# PLC_NanoPI.net
KiCad netlist of a schematic drawn in Altium Designer
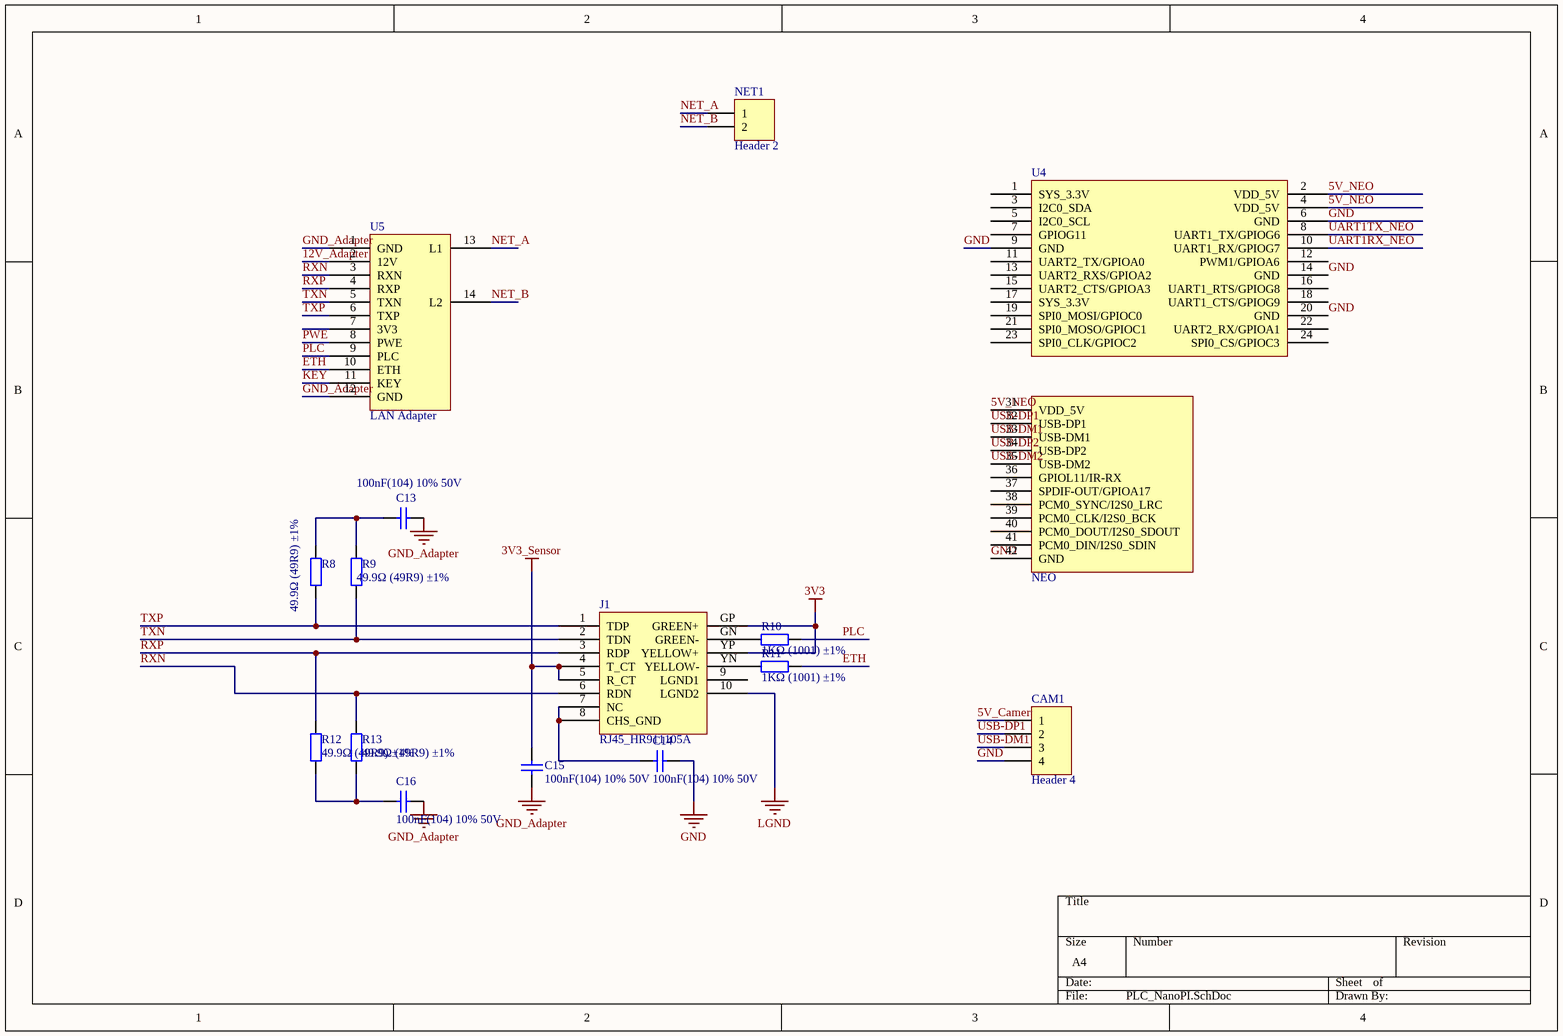
[diagram p0: PLC_NanoPI.SchDoc]

(export (version "E")
  (design (tool "Eeschema 10.0.6"))
  (components
    (comp (ref "C13")
      (value "100nF(104) 10% 50V")
      (footprint "0603_C")
      (description "贴片电容")
      (libsource (lib "Miscellaneous Devices LC") (part "0805 100nF(104) 10% 50V"))
    )
    (comp (ref "C14")
      (value "100nF(104) 10% 50V")
      (footprint "0603-cap")
      (description "贴片电容")
      (libsource (lib "Miscellaneous Devices LC") (part "0805 100nF(104) 10% 50V"))
    )
    (comp (ref "C15")
      (value "100nF(104) 10% 50V")
      (footprint "0603_C")
      (description "贴片电容")
      (libsource (lib "Miscellaneous Devices LC") (part "0805 100nF(104) 10% 50V"))
    )
    (comp (ref "C16")
      (value "100nF(104) 10% 50V")
      (footprint "0603_C")
      (description "贴片电容")
      (libsource (lib "Miscellaneous Devices LC") (part "0805 100nF(104) 10% 50V"))
    )
    (comp (ref "CAM1")
      (value "Header 4")
      (footprint "XH2.54_4P")
      (description "Header, 4-Pin")
      (fields (field (name "PUBLISHER") "Altium Limited"))
      (libsource (lib "Miscellaneous Connectors") (part "Header 4"))
    )
    (comp (ref "J1")
      (value "RJ45_HR911105A")
      (footprint "RJ45_3")
      (libsource (lib "RJ45") (part "RJ45_HR911105A"))
    )
    (comp (ref "NET1")
      (value "Header 2")
      (footprint "XH2.54_2P")
      (description "Header, 2-Pin")
      (fields (field (name "PUBLISHER") "Altium Limited"))
      (libsource (lib "Miscellaneous Connectors") (part "Header 2"))
    )
    (comp (ref "R8")
      (value "49.9Ω (49R9) ±1%")
      (footprint "0603_R")
      (description "贴片电阻")
      (libsource (lib "Miscellaneous Devices LC") (part "0805 49.9Ω (49R9) 1%"))
    )
    (comp (ref "R9")
      (value "49.9Ω (49R9) ±1%")
      (footprint "0603_R")
      (description "贴片电阻")
      (libsource (lib "Miscellaneous Devices LC") (part "0805 49.9Ω (49R9) 1%"))
    )
    (comp (ref "R10")
      (value "1KΩ (1001) ±1%")
      (footprint "0603_R")
      (description "贴片电阻")
      (libsource (lib "Miscellaneous Devices LC") (part "0603 1KΩ (1001) 1%"))
    )
    (comp (ref "R11")
      (value "1KΩ (1001) ±1%")
      (footprint "0603_R")
      (description "贴片电阻")
      (libsource (lib "Miscellaneous Devices LC") (part "0603 1KΩ (1001) 1%"))
    )
    (comp (ref "R12")
      (value "49.9Ω (49R9) ±1%")
      (footprint "0603_R")
      (description "贴片电阻")
      (libsource (lib "Miscellaneous Devices LC") (part "0805 49.9Ω (49R9) 1%"))
    )
    (comp (ref "R13")
      (value "49.9Ω (49R9) ±1%")
      (footprint "0603_R")
      (description "贴片电阻")
      (libsource (lib "Miscellaneous Devices LC") (part "0805 49.9Ω (49R9) 1%"))
    )
    (comp (ref "U4") (value "NEO") (footprint "NanoPiNEO") (libsource (lib "NanoPi") (part "NanoPiNEO")))
    (comp (ref "U5")
      (value "LAN Adapter")
      (footprint "LAN Adapter")
      (libsource (lib "Adapter") (part "LAN Adapter"))
    )
  )
  (nets
    (net (code "1") (name "/5V_Camera") (class "Default")
      (node (ref "CAM1") (pin "1") (pinfunction "1_1") (pintype "passive"))
    )
    (net (code "2") (name "/5V_NEO") (class "Default")
      (node (ref "U4") (pin "2") (pinfunction "VDD_5V_2") (pintype "passive"))
      (node (ref "U4") (pin "31") (pinfunction "VDD_5V_31") (pintype "passive"))
      (node (ref "U4") (pin "4") (pinfunction "VDD_5V_4") (pintype "passive"))
    )
    (net (code "3") (name "/12V_Adapter") (class "Default")
      (node (ref "U5") (pin "2") (pinfunction "12V_2") (pintype "passive"))
    )
    (net (code "4") (name "/ETH") (class "Default")
      (node (ref "R11") (pin "2") (pinfunction "2_2") (pintype "passive"))
      (node (ref "U5") (pin "10") (pinfunction "ETH_10") (pintype "passive"))
    )
    (net (code "5") (name "/KEY") (class "Default")
      (node (ref "U5") (pin "11") (pinfunction "KEY_11") (pintype "passive"))
    )
    (net (code "6") (name "/NET_A") (class "Default")
      (node (ref "NET1") (pin "1") (pinfunction "1_1") (pintype "passive"))
      (node (ref "U5") (pin "13") (pinfunction "L1_13") (pintype "passive"))
    )
    (net (code "7") (name "/NET_B") (class "Default")
      (node (ref "NET1") (pin "2") (pinfunction "2_2") (pintype "passive"))
      (node (ref "U5") (pin "14") (pinfunction "L2_14") (pintype "passive"))
    )
    (net (code "8") (name "/PLC") (class "Default")
      (node (ref "R10") (pin "2") (pinfunction "2_2") (pintype "passive"))
      (node (ref "U5") (pin "9") (pinfunction "PLC_9") (pintype "passive"))
    )
    (net (code "9") (name "/PWE") (class "Default")
      (node (ref "U5") (pin "8") (pinfunction "PWE_8") (pintype "passive"))
    )
    (net (code "10") (name "/RXN") (class "Default")
      (node (ref "J1") (pin "6") (pinfunction "RDN_6") (pintype "passive"))
      (node (ref "R13") (pin "2") (pinfunction "2_2") (pintype "passive"))
      (node (ref "U5") (pin "3") (pinfunction "RXN_3") (pintype "passive"))
    )
    (net (code "11") (name "/RXP") (class "Default")
      (node (ref "J1") (pin "3") (pinfunction "RDP_3") (pintype "passive"))
      (node (ref "R12") (pin "2") (pinfunction "2_2") (pintype "passive"))
      (node (ref "U5") (pin "4") (pinfunction "RXP_4") (pintype "passive"))
    )
    (net (code "12") (name "/TXN") (class "Default")
      (node (ref "J1") (pin "2") (pinfunction "TDN_2") (pintype "passive"))
      (node (ref "R9") (pin "1") (pinfunction "1_1") (pintype "passive"))
      (node (ref "U5") (pin "5") (pinfunction "TXN_5") (pintype "passive"))
    )
    (net (code "13") (name "/TXP") (class "Default")
      (node (ref "J1") (pin "1") (pinfunction "TDP_1") (pintype "passive"))
      (node (ref "R8") (pin "1") (pinfunction "1_1") (pintype "passive"))
      (node (ref "U5") (pin "6") (pinfunction "TXP_6") (pintype "passive"))
    )
    (net (code "14") (name "/UART1RX_NEO") (class "Default")
      (node (ref "U4") (pin "10") (pinfunction "UART1_RX/GPIOG7_10") (pintype "passive"))
    )
    (net (code "15") (name "/UART1TX_NEO") (class "Default")
      (node (ref "U4") (pin "8") (pinfunction "UART1_TX/GPIOG6_8") (pintype "passive"))
    )
    (net (code "16") (name "/USB-DM1") (class "Default")
      (node (ref "CAM1") (pin "3") (pinfunction "3_3") (pintype "passive"))
      (node (ref "U4") (pin "33") (pinfunction "USB-DM1_33") (pintype "passive"))
    )
    (net (code "17") (name "/USB-DM2") (class "Default")
      (node (ref "U4") (pin "35") (pinfunction "USB-DM2_35") (pintype "passive"))
    )
    (net (code "18") (name "/USB-DP1") (class "Default")
      (node (ref "CAM1") (pin "2") (pinfunction "2_2") (pintype "passive"))
      (node (ref "U4") (pin "32") (pinfunction "USB-DP1_32") (pintype "passive"))
    )
    (net (code "19") (name "/USB-DP2") (class "Default")
      (node (ref "U4") (pin "34") (pinfunction "USB-DP2_34") (pintype "passive"))
    )
    (net (code "20") (name "3V3") (class "Default")
      (node (ref "J1") (pin "GP") (pinfunction "GREEN+_GP") (pintype "passive"))
      (node (ref "J1") (pin "YP") (pinfunction "YELLOW+_YP") (pintype "passive"))
    )
    (net (code "21") (name "3V3_Sensor") (class "Default")
      (node (ref "C15") (pin "2") (pinfunction "2_2") (pintype "passive"))
      (node (ref "J1") (pin "4") (pinfunction "T_CT_4") (pintype "passive"))
      (node (ref "J1") (pin "5") (pinfunction "R_CT_5") (pintype "passive"))
    )
    (net (code "22") (name "GND") (class "Default")
      (node (ref "C14") (pin "1") (pinfunction "1_1") (pintype "passive"))
      (node (ref "CAM1") (pin "4") (pinfunction "4_4") (pintype "passive"))
      (node (ref "U4") (pin "14") (pinfunction "GND_14") (pintype "passive"))
      (node (ref "U4") (pin "20") (pinfunction "GND_20") (pintype "passive"))
      (node (ref "U4") (pin "42") (pinfunction "GND_42") (pintype "passive"))
      (node (ref "U4") (pin "6") (pinfunction "GND_6") (pintype "passive"))
      (node (ref "U4") (pin "9") (pinfunction "GND_9") (pintype "passive"))
    )
    (net (code "23") (name "GND_Adapter") (class "Default")
      (node (ref "C13") (pin "1") (pinfunction "1_1") (pintype "passive"))
      (node (ref "C15") (pin "1") (pinfunction "1_1") (pintype "passive"))
      (node (ref "C16") (pin "1") (pinfunction "1_1") (pintype "passive"))
      (node (ref "U5") (pin "1") (pinfunction "GND_1") (pintype "passive"))
      (node (ref "U5") (pin "12") (pinfunction "GND_12") (pintype "passive"))
    )
    (net (code "24") (name "LGND") (class "Default")
      (node (ref "J1") (pin "10") (pinfunction "LGND2_10") (pintype "passive"))
    )
    (net (code "25") (name "Net-(C13-Pad2)") (class "Default")
      (node (ref "C13") (pin "2") (pinfunction "2_2") (pintype "passive"))
      (node (ref "R8") (pin "2") (pinfunction "2_2") (pintype "passive"))
      (node (ref "R9") (pin "2") (pinfunction "2_2") (pintype "passive"))
    )
    (net (code "26") (name "Net-(C16-Pad2)") (class "Default")
      (node (ref "C16") (pin "2") (pinfunction "2_2") (pintype "passive"))
      (node (ref "R12") (pin "1") (pinfunction "1_1") (pintype "passive"))
      (node (ref "R13") (pin "1") (pinfunction "1_1") (pintype "passive"))
    )
    (net (code "27") (name "Net-(J1-CHS_GND)") (class "Default")
      (node (ref "C14") (pin "2") (pinfunction "2_2") (pintype "passive"))
      (node (ref "J1") (pin "7") (pinfunction "NC_7") (pintype "passive"))
      (node (ref "J1") (pin "8") (pinfunction "CHS_GND_8") (pintype "passive"))
    )
    (net (code "28") (name "Net-(J1-GREEN-)") (class "Default")
      (node (ref "J1") (pin "GN") (pinfunction "GREEN-_GN") (pintype "passive"))
      (node (ref "R10") (pin "1") (pinfunction "1_1") (pintype "passive"))
    )
    (net (code "29") (name "Net-(J1-YELLOW-)") (class "Default")
      (node (ref "J1") (pin "YN") (pinfunction "YELLOW-_YN") (pintype "passive"))
      (node (ref "R11") (pin "1") (pinfunction "1_1") (pintype "passive"))
    )
    (net (code "30") (name "unconnected-(J1-LGND1-Pad9)") (class "Default")
      (node (ref "J1") (pin "9") (pinfunction "LGND1_9") (pintype "passive"))
    )
    (net (code "31") (name "unconnected-(U4-GPIOG11-Pad7)") (class "Default")
      (node (ref "U4") (pin "7") (pinfunction "GPIOG11_7") (pintype "passive"))
    )
    (net (code "32") (name "unconnected-(U4-GPIOL11{slash}IR-RX-Pad36)") (class "Default")
      (node (ref "U4") (pin "36") (pinfunction "GPIOL11/IR-RX_36") (pintype "passive"))
    )
    (net (code "33") (name "unconnected-(U4-I2C0_SCL-Pad5)") (class "Default")
      (node (ref "U4") (pin "5") (pinfunction "I2C0_SCL_5") (pintype "passive"))
    )
    (net (code "34") (name "unconnected-(U4-I2C0_SDA-Pad3)") (class "Default")
      (node (ref "U4") (pin "3") (pinfunction "I2C0_SDA_3") (pintype "passive"))
    )
    (net (code "35") (name "unconnected-(U4-PCM0_CLK{slash}I2S0_BCK-Pad39)") (class "Default")
      (node (ref "U4") (pin "39") (pinfunction "PCM0_CLK/I2S0_BCK_39") (pintype "passive"))
    )
    (net (code "36") (name "unconnected-(U4-PCM0_DIN{slash}I2S0_SDIN-Pad41)") (class "Default")
      (node (ref "U4") (pin "41") (pinfunction "PCM0_DIN/I2S0_SDIN_41") (pintype "passive"))
    )
    (net (code "37") (name "unconnected-(U4-PCM0_DOUT{slash}I2S0_SDOUT-Pad40)") (class "Default")
      (node (ref "U4") (pin "40") (pinfunction "PCM0_DOUT/I2S0_SDOUT_40") (pintype "passive"))
    )
    (net (code "38") (name "unconnected-(U4-PCM0_SYNC{slash}I2S0_LRC-Pad38)") (class "Default")
      (node (ref "U4") (pin "38") (pinfunction "PCM0_SYNC/I2S0_LRC_38") (pintype "passive"))
    )
    (net (code "39") (name "unconnected-(U4-PWM1{slash}GPIOA6-Pad12)") (class "Default")
      (node (ref "U4") (pin "12") (pinfunction "PWM1/GPIOA6_12") (pintype "passive"))
    )
    (net (code "40") (name "unconnected-(U4-SPDIF-OUT{slash}GPIOA17-Pad37)") (class "Default")
      (node (ref "U4") (pin "37") (pinfunction "SPDIF-OUT/GPIOA17_37") (pintype "passive"))
    )
    (net (code "41") (name "unconnected-(U4-SPI0_CLK{slash}GPIOC2-Pad23)") (class "Default")
      (node (ref "U4") (pin "23") (pinfunction "SPI0_CLK/GPIOC2_23") (pintype "passive"))
    )
    (net (code "42") (name "unconnected-(U4-SPI0_CS{slash}GPIOC3-Pad24)") (class "Default")
      (node (ref "U4") (pin "24") (pinfunction "SPI0_CS/GPIOC3_24") (pintype "passive"))
    )
    (net (code "43") (name "unconnected-(U4-SPI0_MOSI{slash}GPIOC0-Pad19)") (class "Default")
      (node (ref "U4") (pin "19") (pinfunction "SPI0_MOSI/GPIOC0_19") (pintype "passive"))
    )
    (net (code "44") (name "unconnected-(U4-SPI0_MOSO{slash}GPIOC1-Pad21)") (class "Default")
      (node (ref "U4") (pin "21") (pinfunction "SPI0_MOSO/GPIOC1_21") (pintype "passive"))
    )
    (net (code "45") (name "unconnected-(U4-SYS_3.3V-Pad1)") (class "Default")
      (node (ref "U4") (pin "1") (pinfunction "SYS_3.3V_1") (pintype "passive"))
    )
    (net (code "46") (name "unconnected-(U4-SYS_3.3V-Pad17)") (class "Default")
      (node (ref "U4") (pin "17") (pinfunction "SYS_3.3V_17") (pintype "passive"))
    )
    (net (code "47") (name "unconnected-(U4-UART1_CTS{slash}GPIOG9-Pad18)") (class "Default")
      (node (ref "U4") (pin "18") (pinfunction "UART1_CTS/GPIOG9_18") (pintype "passive"))
    )
    (net (code "48") (name "unconnected-(U4-UART1_RTS{slash}GPIOG8-Pad16)") (class "Default")
      (node (ref "U4") (pin "16") (pinfunction "UART1_RTS/GPIOG8_16") (pintype "passive"))
    )
    (net (code "49") (name "unconnected-(U4-UART2_CTS{slash}GPIOA3-Pad15)") (class "Default")
      (node (ref "U4") (pin "15") (pinfunction "UART2_CTS/GPIOA3_15") (pintype "passive"))
    )
    (net (code "50") (name "unconnected-(U4-UART2_RXS{slash}GPIOA2-Pad13)") (class "Default")
      (node (ref "U4") (pin "13") (pinfunction "UART2_RXS/GPIOA2_13") (pintype "passive"))
    )
    (net (code "51") (name "unconnected-(U4-UART2_RX{slash}GPIOA1-Pad22)") (class "Default")
      (node (ref "U4") (pin "22") (pinfunction "UART2_RX/GPIOA1_22") (pintype "passive"))
    )
    (net (code "52") (name "unconnected-(U4-UART2_TX{slash}GPIOA0-Pad11)") (class "Default")
      (node (ref "U4") (pin "11") (pinfunction "UART2_TX/GPIOA0_11") (pintype "passive"))
    )
    (net (code "53") (name "unconnected-(U5-3V3-Pad7)") (class "Default")
      (node (ref "U5") (pin "7") (pinfunction "3V3_7") (pintype "passive"))
    )
  )
)
